# bp_to_avr.net
KiCad netlist of a schematic drawn in EAGLE
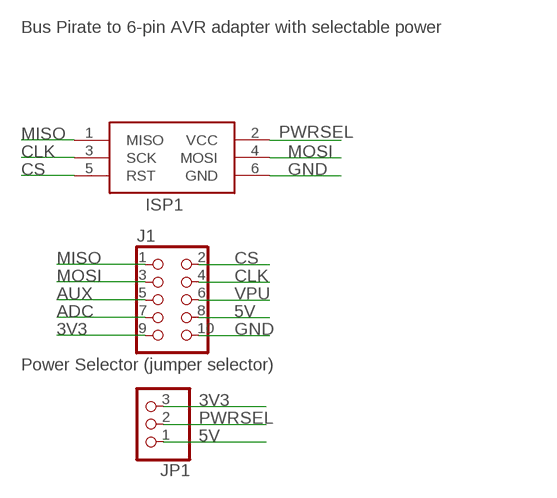
[diagram p0: schematic, sheet 1]

(export (version "E")
  (design (tool "Eeschema 10.0.6"))
  (components
    (comp (ref "ISP1")
      (value "AVRISP-6")
      (footprint "eagle-import:AVRISP")
      (libsource (lib "eagle-import") (part "AVRISP-6"))
    )
    (comp (ref "J1")
      (value "CON_HEADER_2X05-PTH+SHROUDED_B")
      (footprint "eagle-import:PINSHRD_PTH_2X05B")
      (libsource (lib "eagle-import") (part "CON_HEADER_2X05-PTH+SHROUDED_B"))
    )
    (comp (ref "JP1")
      (value "PINHD-1X3")
      (footprint "eagle-import:1X03")
      (libsource (lib "eagle-import") (part "PINHD-1X3"))
    )
  )
  (nets
    (net (code "1") (name "/3V3") (class "Default")
      (node (ref "J1") (pin "9") (pinfunction "9_9") (pintype "passive"))
      (node (ref "JP1") (pin "3") (pinfunction "3_3") (pintype "passive"))
    )
    (net (code "2") (name "/5V") (class "Default")
      (node (ref "J1") (pin "8") (pinfunction "8_8") (pintype "passive"))
      (node (ref "JP1") (pin "1") (pinfunction "1_1") (pintype "passive"))
    )
    (net (code "3") (name "/ADC") (class "Default")
      (node (ref "J1") (pin "7") (pinfunction "7_7") (pintype "passive"))
    )
    (net (code "4") (name "/AUX") (class "Default")
      (node (ref "J1") (pin "5") (pinfunction "5_5") (pintype "passive"))
    )
    (net (code "5") (name "/CLK") (class "Default")
      (node (ref "ISP1") (pin "3") (pinfunction "SCK_3") (pintype "output"))
      (node (ref "J1") (pin "4") (pinfunction "4_4") (pintype "passive"))
    )
    (net (code "6") (name "/CS") (class "Default")
      (node (ref "ISP1") (pin "5") (pinfunction "RST_5") (pintype "output"))
      (node (ref "J1") (pin "2") (pinfunction "2_2") (pintype "passive"))
    )
    (net (code "7") (name "/GND") (class "Default")
      (node (ref "ISP1") (pin "6") (pinfunction "GND_6") (pintype "power_in"))
      (node (ref "J1") (pin "10") (pinfunction "10_10") (pintype "passive"))
    )
    (net (code "8") (name "/MISO") (class "Default")
      (node (ref "ISP1") (pin "1") (pinfunction "MISO_1") (pintype "input"))
      (node (ref "J1") (pin "1") (pinfunction "1_1") (pintype "passive"))
    )
    (net (code "9") (name "/MOSI") (class "Default")
      (node (ref "ISP1") (pin "4") (pinfunction "MOSI_4") (pintype "output"))
      (node (ref "J1") (pin "3") (pinfunction "3_3") (pintype "passive"))
    )
    (net (code "10") (name "/PWRSEL") (class "Default")
      (node (ref "ISP1") (pin "2") (pinfunction "VCC_2") (pintype "power_in"))
      (node (ref "JP1") (pin "2") (pinfunction "2_2") (pintype "passive"))
    )
    (net (code "11") (name "/VPU") (class "Default")
      (node (ref "J1") (pin "6") (pinfunction "6_6") (pintype "passive"))
    )
  )
)
